# ME433.net
KiCad netlist of a schematic drawn in EAGLE
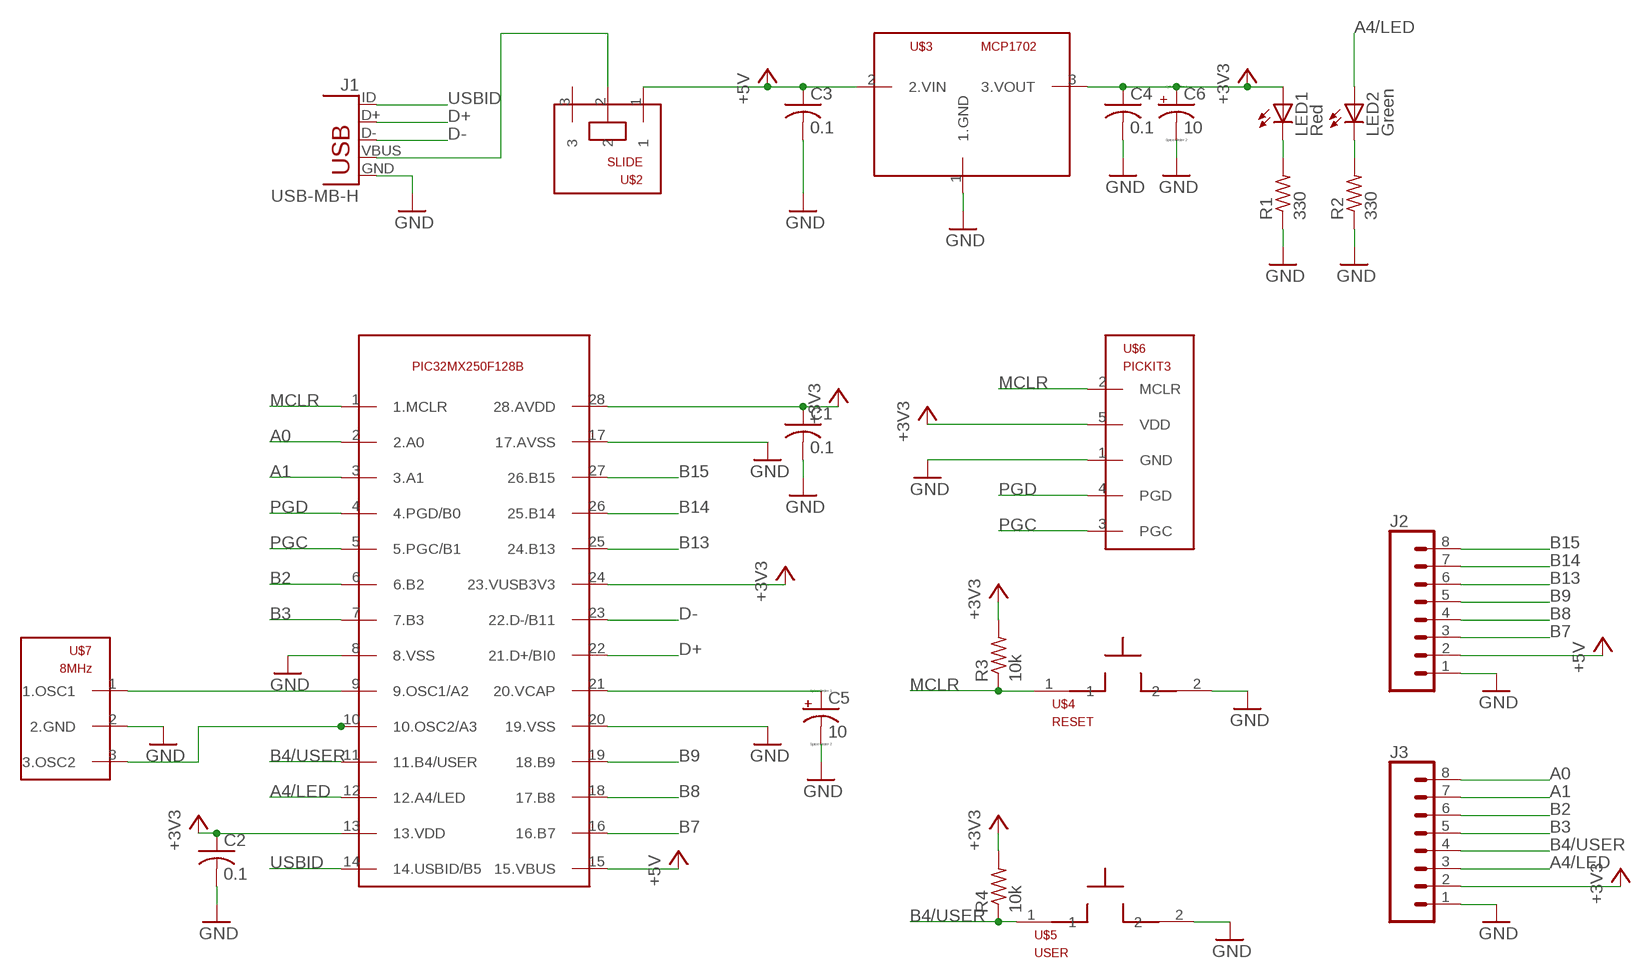
[diagram p0: schematic, sheet 1]

(export (version "E")
  (design (tool "Eeschema 10.0.6"))
  (components
    (comp (ref "C1")
      (value "0.1")
      (footprint "eagle-import:C025-025X050")
      (libsource (lib "eagle-import") (part "C-US025-025X050"))
    )
    (comp (ref "C2")
      (value "0.1")
      (footprint "eagle-import:C025-025X050")
      (libsource (lib "eagle-import") (part "C-US025-025X050"))
    )
    (comp (ref "C3")
      (value "0.1")
      (footprint "eagle-import:C025-025X050")
      (libsource (lib "eagle-import") (part "C-US025-025X050"))
    )
    (comp (ref "C4")
      (value "0.1")
      (footprint "eagle-import:C025-025X050")
      (libsource (lib "eagle-import") (part "C-US025-025X050"))
    )
    (comp (ref "C5")
      (value "10")
      (footprint "eagle-import:B45181B")
      (libsource (lib "eagle-import") (part "CPOL-USB45181B"))
    )
    (comp (ref "C6")
      (value "10")
      (footprint "eagle-import:B45181B")
      (libsource (lib "eagle-import") (part "CPOL-USB45181B"))
    )
    (comp (ref "J1")
      (value "USB-MB-H")
      (footprint "eagle-import:USB-MB-H")
      (libsource (lib "eagle-import") (part "USB-MB-H"))
    )
    (comp (ref "J2")
      (value "CONN_08\"")
      (footprint "eagle-import:1X08")
      (libsource (lib "eagle-import") (part "CONN_08{dblquote}"))
    )
    (comp (ref "J3")
      (value "CONN_08\"")
      (footprint "eagle-import:1X08")
      (libsource (lib "eagle-import") (part "CONN_08{dblquote}"))
    )
    (comp (ref "LED1")
      (value "Red")
      (footprint "eagle-import:LED3MM")
      (libsource (lib "eagle-import") (part "LED3MM"))
    )
    (comp (ref "LED2")
      (value "Green")
      (footprint "eagle-import:LED3MM")
      (libsource (lib "eagle-import") (part "LED3MM"))
    )
    (comp (ref "R1")
      (value "330")
      (footprint "eagle-import:0207_10")
      (libsource (lib "eagle-import") (part "R-US_0207/10"))
    )
    (comp (ref "R2")
      (value "330")
      (footprint "eagle-import:0207_10")
      (libsource (lib "eagle-import") (part "R-US_0207/10"))
    )
    (comp (ref "R3")
      (value "10k")
      (footprint "eagle-import:0207_10")
      (libsource (lib "eagle-import") (part "R-US_0207/10"))
    )
    (comp (ref "R4")
      (value "10k")
      (footprint "eagle-import:0207_10")
      (libsource (lib "eagle-import") (part "R-US_0207/10"))
    )
    (comp (ref "U$1")
      (value "PIC32MX250F128B")
      (footprint "eagle-import:DIL28-3")
      (libsource (lib "eagle-import") (part "PIC32MX250F128B"))
    )
    (comp (ref "U$2")
      (value "SLIDE")
      (footprint "eagle-import:SLIDE")
      (libsource (lib "eagle-import") (part "SLIDE"))
    )
    (comp (ref "U$3")
      (value "MCP1702")
      (footprint "eagle-import:TO92")
      (libsource (lib "eagle-import") (part "MCP1702"))
    )
    (comp (ref "U$4")
      (value "RESET")
      (footprint "eagle-import:PB")
      (libsource (lib "eagle-import") (part "PB"))
    )
    (comp (ref "U$5")
      (value "USER")
      (footprint "eagle-import:PB")
      (libsource (lib "eagle-import") (part "PB"))
    )
    (comp (ref "U$6")
      (value "PICKIT3")
      (footprint "eagle-import:1X05")
      (libsource (lib "eagle-import") (part "PICKIT3"))
    )
    (comp (ref "U$7")
      (value "8MHz")
      (footprint "eagle-import:OSC")
      (libsource (lib "eagle-import") (part "OSC"))
    )
  )
  (nets
    (net (code "1") (name "+3V3") (class "Default")
      (node (ref "C1") (pin "1") (pinfunction "1_1") (pintype "passive"))
      (node (ref "C2") (pin "1") (pinfunction "1_1") (pintype "passive"))
      (node (ref "C4") (pin "1") (pinfunction "1_1") (pintype "passive"))
      (node (ref "C6") (pin "+") (pinfunction "+_+") (pintype "passive"))
      (node (ref "J3") (pin "2") (pinfunction "2_2") (pintype "passive"))
      (node (ref "LED1") (pin "A") (pinfunction "A_A") (pintype "passive"))
      (node (ref "R3") (pin "2") (pinfunction "2_2") (pintype "passive"))
      (node (ref "R4") (pin "2") (pinfunction "2_2") (pintype "passive"))
      (node (ref "U$1") (pin "13") (pinfunction "13.VDD_13") (pintype "bidirectional"))
      (node (ref "U$1") (pin "24") (pinfunction "23.VUSB3V3_24") (pintype "bidirectional"))
      (node (ref "U$1") (pin "28") (pinfunction "28.AVDD_28") (pintype "bidirectional"))
      (node (ref "U$3") (pin "3") (pinfunction "3.VOUT_3") (pintype "bidirectional"))
      (node (ref "U$6") (pin "5") (pinfunction "VDD_5") (pintype "bidirectional"))
    )
    (net (code "2") (name "+5V") (class "Default")
      (node (ref "C3") (pin "1") (pinfunction "1_1") (pintype "passive"))
      (node (ref "J2") (pin "2") (pinfunction "2_2") (pintype "passive"))
      (node (ref "U$1") (pin "15") (pinfunction "15.VBUS_15") (pintype "bidirectional"))
      (node (ref "U$2") (pin "1") (pinfunction "1_1") (pintype "bidirectional"))
      (node (ref "U$3") (pin "2") (pinfunction "2.VIN_2") (pintype "bidirectional"))
    )
    (net (code "3") (name "/A0") (class "Default")
      (node (ref "J3") (pin "8") (pinfunction "8_8") (pintype "passive"))
      (node (ref "U$1") (pin "2") (pinfunction "2.A0_2") (pintype "bidirectional"))
    )
    (net (code "4") (name "/A1") (class "Default")
      (node (ref "J3") (pin "7") (pinfunction "7_7") (pintype "passive"))
      (node (ref "U$1") (pin "3") (pinfunction "3.A1_3") (pintype "bidirectional"))
    )
    (net (code "5") (name "/A4{slash}LED") (class "Default")
      (node (ref "J3") (pin "3") (pinfunction "3_3") (pintype "passive"))
      (node (ref "LED2") (pin "A") (pinfunction "A_A") (pintype "passive"))
      (node (ref "U$1") (pin "12") (pinfunction "12.A4/LED_12") (pintype "bidirectional"))
    )
    (net (code "6") (name "/B2") (class "Default")
      (node (ref "J3") (pin "6") (pinfunction "6_6") (pintype "passive"))
      (node (ref "U$1") (pin "6") (pinfunction "6.B2_6") (pintype "bidirectional"))
    )
    (net (code "7") (name "/B3") (class "Default")
      (node (ref "J3") (pin "5") (pinfunction "5_5") (pintype "passive"))
      (node (ref "U$1") (pin "7") (pinfunction "7.B3_7") (pintype "bidirectional"))
    )
    (net (code "8") (name "/B4{slash}USER") (class "Default")
      (node (ref "J3") (pin "4") (pinfunction "4_4") (pintype "passive"))
      (node (ref "R4") (pin "1") (pinfunction "1_1") (pintype "passive"))
      (node (ref "U$1") (pin "11") (pinfunction "11.B4/USER_11") (pintype "bidirectional"))
      (node (ref "U$5") (pin "1") (pinfunction "1_1") (pintype "bidirectional"))
    )
    (net (code "9") (name "/B7") (class "Default")
      (node (ref "J2") (pin "3") (pinfunction "3_3") (pintype "passive"))
      (node (ref "U$1") (pin "16") (pinfunction "16.B7_16") (pintype "bidirectional"))
    )
    (net (code "10") (name "/B8") (class "Default")
      (node (ref "J2") (pin "4") (pinfunction "4_4") (pintype "passive"))
      (node (ref "U$1") (pin "18") (pinfunction "17.B8_18") (pintype "bidirectional"))
    )
    (net (code "11") (name "/B9") (class "Default")
      (node (ref "J2") (pin "5") (pinfunction "5_5") (pintype "passive"))
      (node (ref "U$1") (pin "19") (pinfunction "18.B9_19") (pintype "bidirectional"))
    )
    (net (code "12") (name "/B13") (class "Default")
      (node (ref "J2") (pin "6") (pinfunction "6_6") (pintype "passive"))
      (node (ref "U$1") (pin "25") (pinfunction "24.B13_25") (pintype "bidirectional"))
    )
    (net (code "13") (name "/B14") (class "Default")
      (node (ref "J2") (pin "7") (pinfunction "7_7") (pintype "passive"))
      (node (ref "U$1") (pin "26") (pinfunction "25.B14_26") (pintype "bidirectional"))
    )
    (net (code "14") (name "/B15") (class "Default")
      (node (ref "J2") (pin "8") (pinfunction "8_8") (pintype "passive"))
      (node (ref "U$1") (pin "27") (pinfunction "26.B15_27") (pintype "bidirectional"))
    )
    (net (code "15") (name "/D+") (class "Default")
      (node (ref "J1") (pin "D+") (pinfunction "D+_D+") (pintype "bidirectional"))
      (node (ref "U$1") (pin "22") (pinfunction "21.D+/BI0_22") (pintype "bidirectional"))
    )
    (net (code "16") (name "/D-") (class "Default")
      (node (ref "J1") (pin "D-") (pinfunction "D-_D-") (pintype "bidirectional"))
      (node (ref "U$1") (pin "23") (pinfunction "22.D-/B11_23") (pintype "bidirectional"))
    )
    (net (code "17") (name "/MCLR") (class "Default")
      (node (ref "R3") (pin "1") (pinfunction "1_1") (pintype "passive"))
      (node (ref "U$1") (pin "1") (pinfunction "1.MCLR_1") (pintype "bidirectional"))
      (node (ref "U$4") (pin "1") (pinfunction "1_1") (pintype "bidirectional"))
      (node (ref "U$6") (pin "2") (pinfunction "MCLR_2") (pintype "bidirectional"))
    )
    (net (code "18") (name "/PGC") (class "Default")
      (node (ref "U$1") (pin "5") (pinfunction "5.PGC/B1_5") (pintype "bidirectional"))
      (node (ref "U$6") (pin "3") (pinfunction "PGC_3") (pintype "bidirectional"))
    )
    (net (code "19") (name "/PGD") (class "Default")
      (node (ref "U$1") (pin "4") (pinfunction "4.PGD/B0_4") (pintype "bidirectional"))
      (node (ref "U$6") (pin "4") (pinfunction "PGD_4") (pintype "bidirectional"))
    )
    (net (code "20") (name "/USBID") (class "Default")
      (node (ref "J1") (pin "ID") (pinfunction "ID_ID") (pintype "bidirectional"))
      (node (ref "U$1") (pin "14") (pinfunction "14.USBID/B5_14") (pintype "bidirectional"))
    )
    (net (code "21") (name "GND") (class "Default")
      (node (ref "C1") (pin "2") (pinfunction "2_2") (pintype "passive"))
      (node (ref "C2") (pin "2") (pinfunction "2_2") (pintype "passive"))
      (node (ref "C3") (pin "2") (pinfunction "2_2") (pintype "passive"))
      (node (ref "C4") (pin "2") (pinfunction "2_2") (pintype "passive"))
      (node (ref "C5") (pin "-") (pinfunction "-_-") (pintype "passive"))
      (node (ref "C6") (pin "-") (pinfunction "-_-") (pintype "passive"))
      (node (ref "J1") (pin "GND") (pinfunction "GND_GND") (pintype "bidirectional"))
      (node (ref "J2") (pin "1") (pinfunction "1_1") (pintype "passive"))
      (node (ref "J3") (pin "1") (pinfunction "1_1") (pintype "passive"))
      (node (ref "R1") (pin "1") (pinfunction "1_1") (pintype "passive"))
      (node (ref "R2") (pin "1") (pinfunction "1_1") (pintype "passive"))
      (node (ref "U$1") (pin "17") (pinfunction "17.AVSS_17") (pintype "bidirectional"))
      (node (ref "U$1") (pin "20") (pinfunction "19.VSS_20") (pintype "bidirectional"))
      (node (ref "U$1") (pin "8") (pinfunction "8.VSS_8") (pintype "bidirectional"))
      (node (ref "U$3") (pin "1") (pinfunction "1.GND_1") (pintype "bidirectional"))
      (node (ref "U$4") (pin "2") (pinfunction "2_2") (pintype "bidirectional"))
      (node (ref "U$5") (pin "2") (pinfunction "2_2") (pintype "bidirectional"))
      (node (ref "U$6") (pin "1") (pinfunction "GND_1") (pintype "bidirectional"))
      (node (ref "U$7") (pin "2") (pinfunction "2.GND_2") (pintype "bidirectional"))
    )
    (net (code "22") (name "Net-(J1-PadVBUS)") (class "Default")
      (node (ref "J1") (pin "VBUS") (pinfunction "VBUS_VBUS") (pintype "bidirectional"))
      (node (ref "U$2") (pin "2") (pinfunction "2_2") (pintype "bidirectional"))
    )
    (net (code "23") (name "Net-(LED1-C)") (class "Default")
      (node (ref "LED1") (pin "K") (pinfunction "C_K") (pintype "passive"))
      (node (ref "R1") (pin "2") (pinfunction "2_2") (pintype "passive"))
    )
    (net (code "24") (name "Net-(LED2-C)") (class "Default")
      (node (ref "LED2") (pin "K") (pinfunction "C_K") (pintype "passive"))
      (node (ref "R2") (pin "2") (pinfunction "2_2") (pintype "passive"))
    )
    (net (code "25") (name "Net-(U$1-9.OSC1{slash}A2)") (class "Default")
      (node (ref "U$1") (pin "9") (pinfunction "9.OSC1/A2_9") (pintype "bidirectional"))
      (node (ref "U$7") (pin "1") (pinfunction "1.OSC1_1") (pintype "bidirectional"))
    )
    (net (code "26") (name "Net-(U$1-10.OSC2{slash}A3)") (class "Default")
      (node (ref "U$1") (pin "10") (pinfunction "10.OSC2/A3_10") (pintype "bidirectional"))
      (node (ref "U$7") (pin "3") (pinfunction "3.OSC2_3") (pintype "bidirectional"))
    )
    (net (code "27") (name "Net-(U$1-20.VCAP)") (class "Default")
      (node (ref "C5") (pin "+") (pinfunction "+_+") (pintype "passive"))
      (node (ref "U$1") (pin "21") (pinfunction "20.VCAP_21") (pintype "bidirectional"))
    )
    (net (code "28") (name "unconnected-(U$2-Pad3)") (class "Default")
      (node (ref "U$2") (pin "3") (pinfunction "3_3") (pintype "bidirectional"))
    )
  )
)
